# PSU_Schematic.net
KiCad netlist of a schematic drawn in Altium Designer
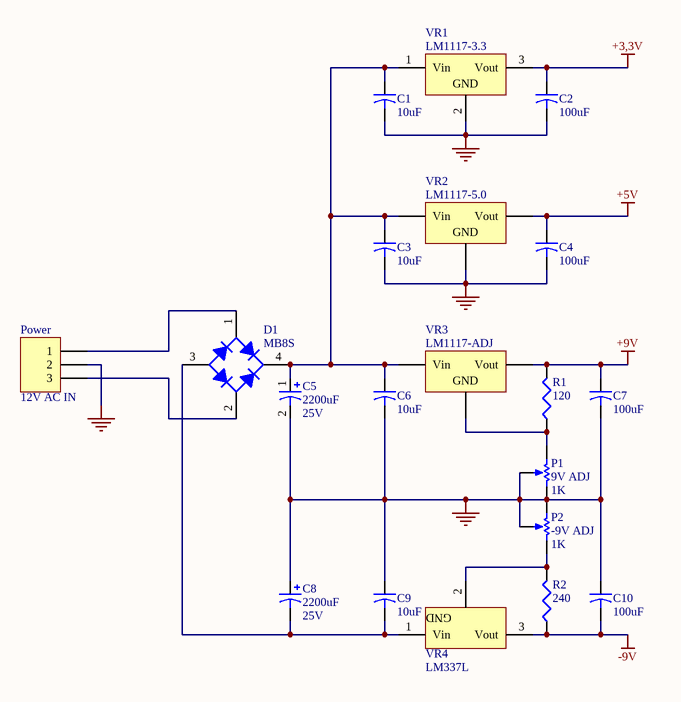
[diagram p0: PSU.Schematic.SchDoc]

(export (version "E")
  (design (tool "Eeschema 10.0.6"))
  (components
    (comp (ref "C1")
      (value "10uF")
      (footprint "CAPC1608N - cap")
      (description "Capacitor")
      (fields (field (name "PUBLISHER") "Altium Limited"))
      (libsource (lib "Miscellaneous Devices") (part "Cap2"))
    )
    (comp (ref "C2")
      (value "100uF")
      (footprint "CAPC1608N - cap")
      (description "Capacitor")
      (fields (field (name "PUBLISHER") "Altium Limited"))
      (libsource (lib "Miscellaneous Devices") (part "Cap2"))
    )
    (comp (ref "C3")
      (value "10uF")
      (footprint "CAPC1608N - cap")
      (description "Capacitor")
      (fields (field (name "PUBLISHER") "Altium Limited"))
      (libsource (lib "Miscellaneous Devices") (part "Cap2"))
    )
    (comp (ref "C4")
      (value "100uF")
      (footprint "CAPC1608N - cap")
      (description "Capacitor")
      (fields (field (name "PUBLISHER") "Altium Limited"))
      (libsource (lib "Miscellaneous Devices") (part "Cap2"))
    )
    (comp (ref "C5")
      (value "2200uF")
      (footprint "Condo electro 13")
      (description "Polarized Capacitor (Radial)")
      (fields (field (name "ALTIUM_VALUE") "25V") (field (name "PUBLISHER") "Altium Limited"))
      (libsource (lib "Miscellaneous Devices") (part "Cap Pol1"))
    )
    (comp (ref "C6")
      (value "10uF")
      (footprint "CAPC1608N - cap")
      (description "Capacitor")
      (fields (field (name "PUBLISHER") "Altium Limited"))
      (libsource (lib "Miscellaneous Devices") (part "Cap2"))
    )
    (comp (ref "C7")
      (value "100uF")
      (footprint "CAPC1608N - cap")
      (description "Capacitor")
      (fields (field (name "PUBLISHER") "Altium Limited"))
      (libsource (lib "Miscellaneous Devices") (part "Cap2"))
    )
    (comp (ref "C8")
      (value "2200uF")
      (footprint "Condo electro 13")
      (description "Polarized Capacitor (Radial)")
      (fields (field (name "ALTIUM_VALUE") "25V") (field (name "PUBLISHER") "Altium Limited"))
      (libsource (lib "") (part "Cap Pol1_1"))
    )
    (comp (ref "C9")
      (value "10uF")
      (footprint "CAPC1608N - cap")
      (description "Capacitor")
      (fields (field (name "PUBLISHER") "Altium Limited"))
      (libsource (lib "Miscellaneous Devices") (part "Cap2"))
    )
    (comp (ref "C10")
      (value "100uF")
      (footprint "CAPC1608N - cap")
      (description "Capacitor")
      (fields (field (name "PUBLISHER") "Altium Limited"))
      (libsource (lib "Miscellaneous Devices") (part "Cap2"))
    )
    (comp (ref "D1")
      (value "MB8S")
      (footprint "MB8S")
      (description "Full Wave Diode Bridge")
      (fields (field (name "PUBLISHER") "Altium Limited"))
      (libsource (lib "Miscellaneous Devices") (part "Bridge1"))
    )
    (comp (ref "P1")
      (value "9V ADJ")
      (footprint "BOURNS Trim pot")
      (description "Potentiometer")
      (fields (field (name "ALTIUM_VALUE") "1K") (field (name "PUBLISHER") "Altium Limited"))
      (libsource (lib "Miscellaneous Devices") (part "RPot"))
    )
    (comp (ref "P2")
      (value "-9V ADJ")
      (footprint "BOURNS Trim pot")
      (description "Potentiometer")
      (fields (field (name "ALTIUM_VALUE") "1K") (field (name "PUBLISHER") "Altium Limited"))
      (libsource (lib "Miscellaneous Devices") (part "RPot"))
    )
    (comp (ref "Power")
      (value "12V AC IN")
      (footprint "Header 3")
      (description "Header, 3-Pin")
      (fields (field (name "PUBLISHER") "Altium Limited"))
      (libsource (lib "Miscellaneous Connectors") (part "Header 3"))
    )
    (comp (ref "R1")
      (value "120")
      (footprint "CAPC1608N")
      (description "Resistor")
      (fields (field (name "PUBLISHER") "Altium Limited"))
      (libsource (lib "Miscellaneous Devices") (part "Res3"))
    )
    (comp (ref "R2")
      (value "240")
      (footprint "CAPC1608N")
      (description "Resistor")
      (fields (field (name "PUBLISHER") "Altium Limited"))
      (libsource (lib "Miscellaneous Devices") (part "Res3"))
    )
    (comp (ref "VR1")
      (value "LM1117-3.3")
      (footprint "LM1117-SOT")
      (description "Voltage Regulator")
      (fields (field (name "PUBLISHER") "Altium Limited"))
      (libsource (lib "") (part "Volt Reg_1"))
    )
    (comp (ref "VR2")
      (value "LM1117-5.0")
      (footprint "LM1117-SOT")
      (description "Voltage Regulator")
      (fields (field (name "PUBLISHER") "Altium Limited"))
      (libsource (lib "") (part "Volt Reg_2"))
    )
    (comp (ref "VR3")
      (value "LM1117-ADJ")
      (footprint "LM1117-SOT")
      (description "Voltage Regulator")
      (fields (field (name "PUBLISHER") "Altium Limited"))
      (libsource (lib "Miscellaneous Devices") (part "Volt Reg"))
    )
    (comp (ref "VR4")
      (value "LM337L")
      (footprint "LM337L")
      (description "Voltage Regulator")
      (fields (field (name "PUBLISHER") "Altium Limited"))
      (libsource (lib "") (part "Volt Reg_3"))
    )
  )
  (nets
    (net (code "1") (name "+3,3V") (class "Default")
      (node (ref "C2") (pin "1") (pinfunction "1_1") (pintype "passive"))
      (node (ref "VR1") (pin "3") (pinfunction "Vout_3") (pintype "passive"))
    )
    (net (code "2") (name "+5V") (class "Default")
      (node (ref "C4") (pin "1") (pinfunction "1_1") (pintype "passive"))
      (node (ref "VR2") (pin "3") (pinfunction "Vout_3") (pintype "passive"))
    )
    (net (code "3") (name "+9V") (class "Default")
      (node (ref "C7") (pin "1") (pinfunction "1_1") (pintype "passive"))
      (node (ref "R1") (pin "2") (pinfunction "2_2") (pintype "passive"))
      (node (ref "VR3") (pin "3") (pinfunction "Vout_3") (pintype "passive"))
    )
    (net (code "4") (name "-9V") (class "Default")
      (node (ref "C10") (pin "2") (pinfunction "2_2") (pintype "passive"))
      (node (ref "R2") (pin "1") (pinfunction "1_1") (pintype "passive"))
      (node (ref "VR4") (pin "3") (pinfunction "Vout_3") (pintype "passive"))
    )
    (net (code "5") (name "GND") (class "Default")
      (node (ref "C1") (pin "2") (pinfunction "2_2") (pintype "passive"))
      (node (ref "C10") (pin "1") (pinfunction "1_1") (pintype "passive"))
      (node (ref "C2") (pin "2") (pinfunction "2_2") (pintype "passive"))
      (node (ref "C3") (pin "2") (pinfunction "2_2") (pintype "passive"))
      (node (ref "C4") (pin "2") (pinfunction "2_2") (pintype "passive"))
      (node (ref "C5") (pin "2") (pinfunction "2_2") (pintype "passive"))
      (node (ref "C6") (pin "2") (pinfunction "2_2") (pintype "passive"))
      (node (ref "C7") (pin "2") (pinfunction "2_2") (pintype "passive"))
      (node (ref "C8") (pin "1") (pinfunction "1_1") (pintype "passive"))
      (node (ref "C9") (pin "1") (pinfunction "1_1") (pintype "passive"))
      (node (ref "P1") (pin "1") (pinfunction "TOP_1") (pintype "passive"))
      (node (ref "P1") (pin "3") (pinfunction "TAP_3") (pintype "passive"))
      (node (ref "P2") (pin "2") (pinfunction "BOT_2") (pintype "passive"))
      (node (ref "P2") (pin "3") (pinfunction "TAP_3") (pintype "passive"))
      (node (ref "Power") (pin "2") (pinfunction "2_2") (pintype "passive"))
      (node (ref "VR1") (pin "2") (pinfunction "GND_2") (pintype "passive"))
      (node (ref "VR2") (pin "2") (pinfunction "GND_2") (pintype "passive"))
    )
    (net (code "6") (name "Net-(D1-A)") (class "Default")
      (node (ref "C8") (pin "2") (pinfunction "2_2") (pintype "passive"))
      (node (ref "C9") (pin "2") (pinfunction "2_2") (pintype "passive"))
      (node (ref "D1") (pin "3") (pinfunction "A_3") (pintype "passive"))
      (node (ref "VR4") (pin "1") (pinfunction "Vin_1") (pintype "passive"))
    )
    (net (code "7") (name "Net-(D1-C-Pad1)") (class "Default")
      (node (ref "D1") (pin "1") (pinfunction "C_1") (pintype "passive"))
      (node (ref "Power") (pin "1") (pinfunction "1_1") (pintype "passive"))
    )
    (net (code "8") (name "Net-(D1-C-Pad2)") (class "Default")
      (node (ref "D1") (pin "2") (pinfunction "C_2") (pintype "passive"))
      (node (ref "Power") (pin "3") (pinfunction "3_3") (pintype "passive"))
    )
    (net (code "9") (name "Net-(D1-K)") (class "Default")
      (node (ref "C1") (pin "1") (pinfunction "1_1") (pintype "passive"))
      (node (ref "C3") (pin "1") (pinfunction "1_1") (pintype "passive"))
      (node (ref "C5") (pin "1") (pinfunction "1_1") (pintype "passive"))
      (node (ref "C6") (pin "1") (pinfunction "1_1") (pintype "passive"))
      (node (ref "D1") (pin "4") (pinfunction "K_4") (pintype "passive"))
      (node (ref "VR1") (pin "1") (pinfunction "Vin_1") (pintype "passive"))
      (node (ref "VR2") (pin "1") (pinfunction "Vin_1") (pintype "passive"))
      (node (ref "VR3") (pin "1") (pinfunction "Vin_1") (pintype "passive"))
    )
    (net (code "10") (name "Net-(P1-BOT)") (class "Default")
      (node (ref "P1") (pin "2") (pinfunction "BOT_2") (pintype "passive"))
      (node (ref "R1") (pin "1") (pinfunction "1_1") (pintype "passive"))
      (node (ref "VR3") (pin "2") (pinfunction "ADJ_2") (pintype "passive"))
    )
    (net (code "11") (name "Net-(P2-TOP)") (class "Default")
      (node (ref "P2") (pin "1") (pinfunction "TOP_1") (pintype "passive"))
      (node (ref "R2") (pin "2") (pinfunction "2_2") (pintype "passive"))
      (node (ref "VR4") (pin "2") (pinfunction "ADJ_2") (pintype "passive"))
    )
  )
)
